# filterdesing.net
KiCad netlist of a schematic drawn in Altium Designer
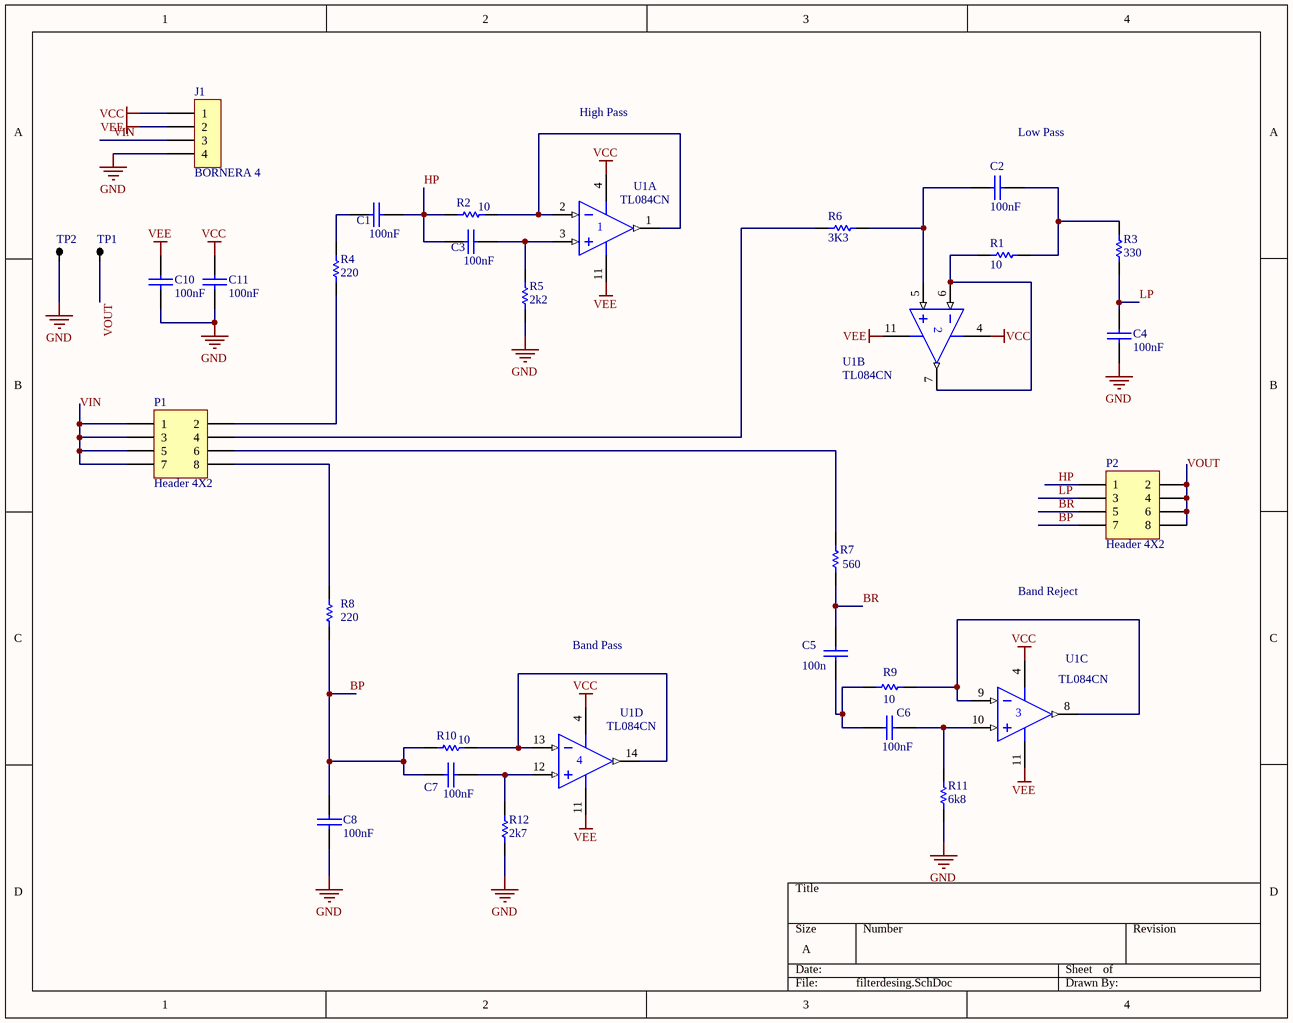
[diagram p0: filterdesing.SchDoc]

(export (version "E")
  (design (tool "Eeschema 10.0.6"))
  (components
    (comp (ref "C1") (value "100nF") (footprint "CAP200") (libsource (lib "LIBEBAL") (part "CAP")))
    (comp (ref "C2") (value "100nF") (footprint "CAP200") (libsource (lib "LIBEBAL") (part "CAP")))
    (comp (ref "C3") (value "100nF") (footprint "CAP200") (libsource (lib "LIBEBAL") (part "CAP")))
    (comp (ref "C4") (value "100nF") (footprint "CAP200") (libsource (lib "LIBEBAL") (part "CAP")))
    (comp (ref "C5") (value "100n") (footprint "CAP200") (libsource (lib "LIBEBAL") (part "CAP")))
    (comp (ref "C6") (value "100nF") (footprint "CAP200") (libsource (lib "LIBEBAL") (part "CAP")))
    (comp (ref "C7") (value "100nF") (footprint "CAP200") (libsource (lib "LIBEBAL") (part "CAP")))
    (comp (ref "C8") (value "100nF") (footprint "CAP200") (libsource (lib "LIBEBAL") (part "CAP")))
    (comp (ref "C10") (value "100nF") (footprint "CAP200") (libsource (lib "LIBEBAL") (part "CAP")))
    (comp (ref "C11") (value "100nF") (footprint "CAP200") (libsource (lib "LIBEBAL") (part "CAP")))
    (comp (ref "J1")
      (value "BORNERA 4")
      (footprint "BORNERA4")
      (libsource (lib "LIBEBAL") (part "BORNERA 4"))
    )
    (comp (ref "P1")
      (value "Header 4X2")
      (footprint "HDR2X4")
      (description "Header, 4-Pin, Dual row")
      (fields (field (name "PUBLISHER") "Altium Limited"))
      (libsource (lib "Miscellaneous Connectors") (part "Header 4X2"))
    )
    (comp (ref "P2")
      (value "Header 4X2")
      (footprint "HDR2X4")
      (description "Header, 4-Pin, Dual row")
      (fields (field (name "PUBLISHER") "Altium Limited"))
      (libsource (lib "Miscellaneous Connectors") (part "Header 4X2"))
    )
    (comp (ref "R1") (value "10") (footprint "RES400") (libsource (lib "LIBEBAL") (part "RES")))
    (comp (ref "R2") (value "10") (footprint "RES400") (libsource (lib "LIBEBAL") (part "RES")))
    (comp (ref "R3") (value "330") (footprint "RES400") (libsource (lib "LIBEBAL") (part "RES")))
    (comp (ref "R4") (value "220") (footprint "RES400") (libsource (lib "LIBEBAL") (part "RES")))
    (comp (ref "R5") (value "2k2") (footprint "RES400") (libsource (lib "LIBEBAL") (part "RES")))
    (comp (ref "R6") (value "3K3") (footprint "RES400") (libsource (lib "LIBEBAL") (part "RES")))
    (comp (ref "R7") (value "560") (footprint "RES400") (libsource (lib "LIBEBAL") (part "RES")))
    (comp (ref "R8") (value "220") (footprint "RES400") (libsource (lib "LIBEBAL") (part "RES")))
    (comp (ref "R9") (value "10") (footprint "RES400") (libsource (lib "LIBEBAL") (part "RES")))
    (comp (ref "R10") (value "10") (footprint "RES400") (libsource (lib "LIBEBAL") (part "RES")))
    (comp (ref "R11") (value "6k8") (footprint "RES400") (libsource (lib "LIBEBAL") (part "RES")))
    (comp (ref "R12") (value "2k7") (footprint "RES400") (libsource (lib "LIBEBAL") (part "RES")))
    (comp (ref "TP1") (value "~") (footprint "TPTH") (libsource (lib "LIBEBAL") (part "TP")))
    (comp (ref "TP2") (value "~") (footprint "TPTH") (libsource (lib "LIBEBAL") (part "TP")))
    (comp (ref "U1")
      (value "TL084CN")
      (footprint "646-06")
      (description "JFET-Input Operational Amplifier")
      (fields (field (name "PUBLISHER") "Altium Limited"))
      (libsource (lib "Motorola Amplifier Operational Amplifier") (part "TL084CN"))
    )
  )
  (nets
    (net (code "1") (name "/BP") (class "Default")
      (node (ref "C7") (pin "1") (pinfunction "1_1") (pintype "passive"))
      (node (ref "C8") (pin "2") (pinfunction "2_2") (pintype "passive"))
      (node (ref "P2") (pin "7") (pinfunction "7_7") (pintype "passive"))
      (node (ref "R10") (pin "2") (pinfunction "2_2") (pintype "passive"))
      (node (ref "R8") (pin "1") (pinfunction "1_1") (pintype "passive"))
    )
    (net (code "2") (name "/BR") (class "Default")
      (node (ref "C5") (pin "2") (pinfunction "2_2") (pintype "passive"))
      (node (ref "P2") (pin "5") (pinfunction "5_5") (pintype "passive"))
      (node (ref "R7") (pin "1") (pinfunction "1_1") (pintype "passive"))
    )
    (net (code "3") (name "/HP") (class "Default")
      (node (ref "C1") (pin "2") (pinfunction "2_2") (pintype "passive"))
      (node (ref "C3") (pin "1") (pinfunction "1_1") (pintype "passive"))
      (node (ref "P2") (pin "1") (pinfunction "1_1") (pintype "passive"))
      (node (ref "R2") (pin "1") (pinfunction "1_1") (pintype "passive"))
    )
    (net (code "4") (name "/LP") (class "Default")
      (node (ref "C4") (pin "2") (pinfunction "2_2") (pintype "passive"))
      (node (ref "P2") (pin "3") (pinfunction "3_3") (pintype "passive"))
      (node (ref "R3") (pin "2") (pinfunction "2_2") (pintype "passive"))
    )
    (net (code "5") (name "/VIN") (class "Default")
      (node (ref "J1") (pin "3") (pinfunction "3_3") (pintype "passive"))
      (node (ref "P1") (pin "1") (pinfunction "1_1") (pintype "passive"))
      (node (ref "P1") (pin "3") (pinfunction "3_3") (pintype "passive"))
      (node (ref "P1") (pin "5") (pinfunction "5_5") (pintype "passive"))
      (node (ref "P1") (pin "7") (pinfunction "7_7") (pintype "passive"))
    )
    (net (code "6") (name "/VOUT") (class "Default")
      (node (ref "P2") (pin "2") (pinfunction "2_2") (pintype "passive"))
      (node (ref "P2") (pin "4") (pinfunction "4_4") (pintype "passive"))
      (node (ref "P2") (pin "6") (pinfunction "6_6") (pintype "passive"))
      (node (ref "P2") (pin "8") (pinfunction "8_8") (pintype "passive"))
      (node (ref "TP1") (pin "1") (pinfunction "1_1") (pintype "passive"))
    )
    (net (code "7") (name "GND") (class "Default")
      (node (ref "C10") (pin "1") (pinfunction "1_1") (pintype "passive"))
      (node (ref "C11") (pin "1") (pinfunction "1_1") (pintype "passive"))
      (node (ref "C4") (pin "1") (pinfunction "1_1") (pintype "passive"))
      (node (ref "C8") (pin "1") (pinfunction "1_1") (pintype "passive"))
      (node (ref "J1") (pin "4") (pinfunction "4_4") (pintype "passive"))
      (node (ref "R11") (pin "2") (pinfunction "2_2") (pintype "passive"))
      (node (ref "R12") (pin "1") (pinfunction "1_1") (pintype "passive"))
      (node (ref "R5") (pin "1") (pinfunction "1_1") (pintype "passive"))
      (node (ref "TP2") (pin "1") (pinfunction "1_1") (pintype "passive"))
    )
    (net (code "8") (name "Net-(C1-Pad1)") (class "Default")
      (node (ref "C1") (pin "1") (pinfunction "1_1") (pintype "passive"))
      (node (ref "R4") (pin "2") (pinfunction "2_2") (pintype "passive"))
    )
    (net (code "9") (name "Net-(C2-Pad2)") (class "Default")
      (node (ref "C2") (pin "2") (pinfunction "2_2") (pintype "passive"))
      (node (ref "R1") (pin "1") (pinfunction "1_1") (pintype "passive"))
      (node (ref "R3") (pin "1") (pinfunction "1_1") (pintype "passive"))
    )
    (net (code "10") (name "Net-(C5-Pad1)") (class "Default")
      (node (ref "C5") (pin "1") (pinfunction "1_1") (pintype "passive"))
      (node (ref "C6") (pin "1") (pinfunction "1_1") (pintype "passive"))
      (node (ref "R9") (pin "1") (pinfunction "1_1") (pintype "passive"))
    )
    (net (code "11") (name "Net-(P1-Pad2)") (class "Default")
      (node (ref "P1") (pin "2") (pinfunction "2_2") (pintype "passive"))
      (node (ref "R4") (pin "1") (pinfunction "1_1") (pintype "passive"))
    )
    (net (code "12") (name "Net-(P1-Pad4)") (class "Default")
      (node (ref "P1") (pin "4") (pinfunction "4_4") (pintype "passive"))
      (node (ref "R6") (pin "1") (pinfunction "1_1") (pintype "passive"))
    )
    (net (code "13") (name "Net-(P1-Pad6)") (class "Default")
      (node (ref "P1") (pin "6") (pinfunction "6_6") (pintype "passive"))
      (node (ref "R7") (pin "2") (pinfunction "2_2") (pintype "passive"))
    )
    (net (code "14") (name "Net-(P1-Pad8)") (class "Default")
      (node (ref "P1") (pin "8") (pinfunction "8_8") (pintype "passive"))
      (node (ref "R8") (pin "2") (pinfunction "2_2") (pintype "passive"))
    )
    (net (code "15") (name "Net-(U1A-IN+)") (class "Default")
      (node (ref "C3") (pin "2") (pinfunction "2_2") (pintype "passive"))
      (node (ref "R5") (pin "2") (pinfunction "2_2") (pintype "passive"))
      (node (ref "U1") (pin "3") (pinfunction "IN+_3") (pintype "input"))
    )
    (net (code "16") (name "Net-(U1A-IN-)") (class "Default")
      (node (ref "R2") (pin "2") (pinfunction "2_2") (pintype "passive"))
      (node (ref "U1") (pin "1") (pinfunction "OUT_1") (pintype "output"))
      (node (ref "U1") (pin "2") (pinfunction "IN-_2") (pintype "input"))
    )
    (net (code "17") (name "Net-(U1B-IN+)") (class "Default")
      (node (ref "C2") (pin "1") (pinfunction "1_1") (pintype "passive"))
      (node (ref "R6") (pin "2") (pinfunction "2_2") (pintype "passive"))
      (node (ref "U1") (pin "5") (pinfunction "IN+_5") (pintype "input"))
    )
    (net (code "18") (name "Net-(U1B-IN-)") (class "Default")
      (node (ref "R1") (pin "2") (pinfunction "2_2") (pintype "passive"))
      (node (ref "U1") (pin "6") (pinfunction "IN-_6") (pintype "input"))
      (node (ref "U1") (pin "7") (pinfunction "OUT_7") (pintype "output"))
    )
    (net (code "19") (name "Net-(U1C-IN+)") (class "Default")
      (node (ref "C6") (pin "2") (pinfunction "2_2") (pintype "passive"))
      (node (ref "R11") (pin "1") (pinfunction "1_1") (pintype "passive"))
      (node (ref "U1") (pin "10") (pinfunction "IN+_10") (pintype "input"))
    )
    (net (code "20") (name "Net-(U1C-IN-)") (class "Default")
      (node (ref "R9") (pin "2") (pinfunction "2_2") (pintype "passive"))
      (node (ref "U1") (pin "8") (pinfunction "OUT_8") (pintype "output"))
      (node (ref "U1") (pin "9") (pinfunction "IN-_9") (pintype "input"))
    )
    (net (code "21") (name "Net-(U1D-IN+)") (class "Default")
      (node (ref "C7") (pin "2") (pinfunction "2_2") (pintype "passive"))
      (node (ref "R12") (pin "2") (pinfunction "2_2") (pintype "passive"))
      (node (ref "U1") (pin "12") (pinfunction "IN+_12") (pintype "input"))
    )
    (net (code "22") (name "Net-(U1D-IN-)") (class "Default")
      (node (ref "R10") (pin "1") (pinfunction "1_1") (pintype "passive"))
      (node (ref "U1") (pin "13") (pinfunction "IN-_13") (pintype "input"))
      (node (ref "U1") (pin "14") (pinfunction "OUT_14") (pintype "output"))
    )
    (net (code "23") (name "VCC") (class "Default")
      (node (ref "C11") (pin "2") (pinfunction "2_2") (pintype "passive"))
      (node (ref "J1") (pin "1") (pinfunction "1_1") (pintype "passive"))
      (node (ref "U1") (pin "4") (pinfunction "V+_4") (pintype "power_in"))
    )
    (net (code "24") (name "VEE") (class "Default")
      (node (ref "C10") (pin "2") (pinfunction "2_2") (pintype "passive"))
      (node (ref "J1") (pin "2") (pinfunction "2_2") (pintype "passive"))
      (node (ref "U1") (pin "11") (pinfunction "V-_11") (pintype "power_in"))
    )
  )
)
